# CompoundPeripheral.net
KiCad netlist of a schematic drawn in Altium Designer
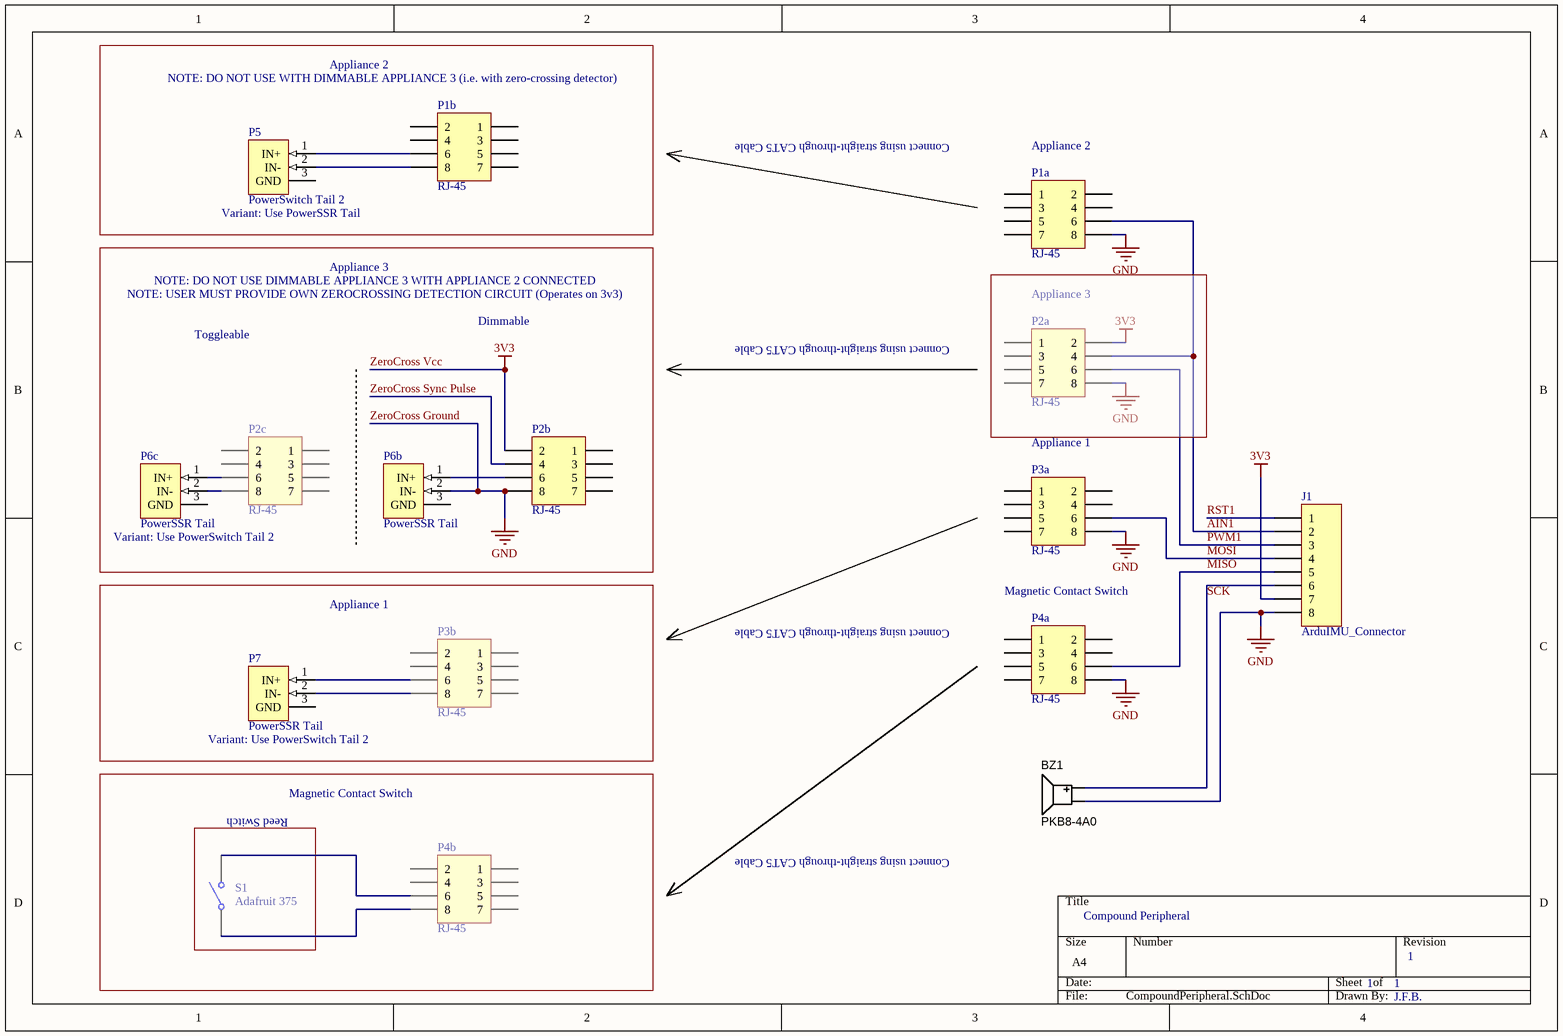
[diagram p0: CompoundPeripheral.SchDoc]

(export (version "E")
  (design (tool "Eeschema 10.0.6"))
  (components
    (comp (ref "BZ1")
      (value "PKB8-4A0")
      (footprint "BUZZER_12.0X8.5MM")
      (description "Speaker, Magnetic Transducer")
      (fields (field (name "MANUFACTURER PART NUMBER 1") "PKB8-4A0"))
      (libsource (lib "PBL - Electromechanical") (part "BZ_12x8.5x6.5_2kHz"))
    )
    (comp (ref "J1")
      (value "ArduIMU_Connector")
      (footprint "HDR1X8")
      (description "Header, 8-Pin")
      (fields (field (name "PUBLISHER") "Altium Limited"))
      (libsource (lib "Miscellaneous Connectors") (part "Header 8"))
    )
    (comp (ref "P1a")
      (value "RJ-45")
      (footprint "HDR2X4")
      (description "Header, 4-Pin, Dual row")
      (fields (field (name "PUBLISHER") "Altium Limited"))
      (libsource (lib "Miscellaneous Connectors") (part "Header 4X2"))
    )
    (comp (ref "P1b")
      (value "RJ-45")
      (footprint "HDR2X4")
      (description "Header, 4-Pin, Dual row")
      (fields (field (name "PUBLISHER") "Altium Limited"))
      (libsource (lib "") (part "Header 4X2_1"))
    )
    (comp (ref "P2a")
      (value "RJ-45")
      (footprint "HDR2X4")
      (description "Header, 4-Pin, Dual row")
      (fields (field (name "PUBLISHER") "Altium Limited"))
      (libsource (lib "Miscellaneous Connectors") (part "Header 4X2"))
    )
    (comp (ref "P2b")
      (value "RJ-45")
      (footprint "HDR2X4")
      (description "Header, 4-Pin, Dual row")
      (fields (field (name "PUBLISHER") "Altium Limited"))
      (libsource (lib "") (part "Header 4X2_1"))
    )
    (comp (ref "P2c")
      (value "RJ-45")
      (footprint "HDR2X4")
      (description "Header, 4-Pin, Dual row")
      (fields (field (name "PUBLISHER") "Altium Limited"))
      (libsource (lib "") (part "Header 4X2_1"))
    )
    (comp (ref "P3a")
      (value "RJ-45")
      (footprint "HDR2X4")
      (description "Header, 4-Pin, Dual row")
      (fields (field (name "PUBLISHER") "Altium Limited"))
      (libsource (lib "Miscellaneous Connectors") (part "Header 4X2"))
    )
    (comp (ref "P3b")
      (value "RJ-45")
      (footprint "HDR2X4")
      (description "Header, 4-Pin, Dual row")
      (fields (field (name "PUBLISHER") "Altium Limited"))
      (libsource (lib "") (part "Header 4X2_1"))
    )
    (comp (ref "P4a")
      (value "RJ-45")
      (footprint "HDR2X4")
      (description "Header, 4-Pin, Dual row")
      (fields (field (name "PUBLISHER") "Altium Limited"))
      (libsource (lib "Miscellaneous Connectors") (part "Header 4X2"))
    )
    (comp (ref "P4b")
      (value "RJ-45")
      (footprint "HDR2X4")
      (description "Header, 4-Pin, Dual row")
      (fields (field (name "PUBLISHER") "Altium Limited"))
      (libsource (lib "") (part "Header 4X2_1"))
    )
    (comp (ref "P5")
      (value "PowerSwitch Tail 2")
      (libsource (lib "CustomPeripherals") (part "PowerSwitch Tail 2"))
    )
    (comp (ref "P6b") (value "PowerSSR Tail") (libsource (lib "CustomPeripherals") (part "PowerSSR Tail")))
    (comp (ref "P6c") (value "PowerSSR Tail") (libsource (lib "CustomPeripherals") (part "PowerSSR Tail")))
    (comp (ref "P7") (value "PowerSSR Tail") (libsource (lib "CustomPeripherals") (part "PowerSSR Tail")))
    (comp (ref "S1")
      (value "Adafruit 375")
      (footprint "SPST-2")
      (description "Single-Pole, Single-Throw Switch")
      (fields (field (name "PUBLISHER") "Altium Limited"))
      (libsource (lib "Miscellaneous Devices") (part "SW-SPST"))
    )
  )
  (nets
    (net (code "1") (name "/AIN1") (class "Default")
      (node (ref "J1") (pin "2") (pinfunction "2_2") (pintype "passive"))
      (node (ref "P1a") (pin "6") (pinfunction "6_6") (pintype "passive"))
      (node (ref "P2a") (pin "4") (pinfunction "4_4") (pintype "passive"))
    )
    (net (code "2") (name "/MISO") (class "Default")
      (node (ref "J1") (pin "5") (pinfunction "5_5") (pintype "passive"))
      (node (ref "P4a") (pin "6") (pinfunction "6_6") (pintype "passive"))
    )
    (net (code "3") (name "/MOSI") (class "Default")
      (node (ref "J1") (pin "4") (pinfunction "4_4") (pintype "passive"))
      (node (ref "P3a") (pin "6") (pinfunction "6_6") (pintype "passive"))
    )
    (net (code "4") (name "/PWM1") (class "Default")
      (node (ref "J1") (pin "3") (pinfunction "3_3") (pintype "passive"))
      (node (ref "P2a") (pin "6") (pinfunction "6_6") (pintype "passive"))
    )
    (net (code "5") (name "/RST1") (class "Default")
      (node (ref "J1") (pin "1") (pinfunction "1_1") (pintype "passive"))
    )
    (net (code "6") (name "/SCK") (class "Default")
      (node (ref "BZ1") (pin "1") (pinfunction "Positive_1") (pintype "passive"))
      (node (ref "J1") (pin "6") (pinfunction "6_6") (pintype "passive"))
    )
    (net (code "7") (name "/ZeroCross Sync Pulse") (class "Default")
      (node (ref "P2b") (pin "4") (pinfunction "4_4") (pintype "passive"))
    )
    (net (code "8") (name "3V3") (class "Default")
      (node (ref "J1") (pin "7") (pinfunction "7_7") (pintype "passive"))
      (node (ref "P2a") (pin "2") (pinfunction "2_2") (pintype "passive"))
      (node (ref "P2b") (pin "2") (pinfunction "2_2") (pintype "passive"))
    )
    (net (code "9") (name "GND") (class "Default")
      (node (ref "BZ1") (pin "2") (pinfunction "Negative_2") (pintype "passive"))
      (node (ref "J1") (pin "8") (pinfunction "8_8") (pintype "passive"))
      (node (ref "P1a") (pin "8") (pinfunction "8_8") (pintype "passive"))
      (node (ref "P2a") (pin "8") (pinfunction "8_8") (pintype "passive"))
      (node (ref "P2b") (pin "8") (pinfunction "8_8") (pintype "passive"))
      (node (ref "P3a") (pin "8") (pinfunction "8_8") (pintype "passive"))
      (node (ref "P4a") (pin "8") (pinfunction "8_8") (pintype "passive"))
      (node (ref "P6b") (pin "2") (pinfunction "IN-_2") (pintype "input"))
    )
    (net (code "10") (name "Net-(P5-IN+)") (class "Default")
      (node (ref "P1b") (pin "6") (pinfunction "6_6") (pintype "passive"))
      (node (ref "P5") (pin "1") (pinfunction "IN+_1") (pintype "input"))
    )
    (net (code "11") (name "Net-(P5-IN-)") (class "Default")
      (node (ref "P1b") (pin "8") (pinfunction "8_8") (pintype "passive"))
      (node (ref "P5") (pin "2") (pinfunction "IN-_2") (pintype "input"))
    )
    (net (code "12") (name "Net-(P6b-IN+)") (class "Default")
      (node (ref "P2b") (pin "6") (pinfunction "6_6") (pintype "passive"))
      (node (ref "P6b") (pin "1") (pinfunction "IN+_1") (pintype "input"))
    )
    (net (code "13") (name "Net-(P6c-IN+)") (class "Default")
      (node (ref "P2c") (pin "6") (pinfunction "6_6") (pintype "passive"))
      (node (ref "P6c") (pin "1") (pinfunction "IN+_1") (pintype "input"))
    )
    (net (code "14") (name "Net-(P6c-IN-)") (class "Default")
      (node (ref "P2c") (pin "8") (pinfunction "8_8") (pintype "passive"))
      (node (ref "P6c") (pin "2") (pinfunction "IN-_2") (pintype "input"))
    )
    (net (code "15") (name "Net-(P7-IN+)") (class "Default")
      (node (ref "P3b") (pin "6") (pinfunction "6_6") (pintype "passive"))
      (node (ref "P7") (pin "1") (pinfunction "IN+_1") (pintype "input"))
    )
    (net (code "16") (name "Net-(P7-IN-)") (class "Default")
      (node (ref "P3b") (pin "8") (pinfunction "8_8") (pintype "passive"))
      (node (ref "P7") (pin "2") (pinfunction "IN-_2") (pintype "input"))
    )
    (net (code "17") (name "Net-(S1-COMMON)") (class "Default")
      (node (ref "P4b") (pin "8") (pinfunction "8_8") (pintype "passive"))
      (node (ref "S1") (pin "1") (pinfunction "COMMON_1") (pintype "passive"))
    )
    (net (code "18") (name "Net-(S1-NO)") (class "Default")
      (node (ref "P4b") (pin "6") (pinfunction "6_6") (pintype "passive"))
      (node (ref "S1") (pin "2") (pinfunction "NO_2") (pintype "passive"))
    )
    (net (code "19") (name "unconnected-(P1a-Pad1)") (class "Default")
      (node (ref "P1a") (pin "1") (pinfunction "1_1") (pintype "passive"))
    )
    (net (code "20") (name "unconnected-(P1a-Pad2)") (class "Default")
      (node (ref "P1a") (pin "2") (pinfunction "2_2") (pintype "passive"))
    )
    (net (code "21") (name "unconnected-(P1a-Pad3)") (class "Default")
      (node (ref "P1a") (pin "3") (pinfunction "3_3") (pintype "passive"))
    )
    (net (code "22") (name "unconnected-(P1a-Pad4)") (class "Default")
      (node (ref "P1a") (pin "4") (pinfunction "4_4") (pintype "passive"))
    )
    (net (code "23") (name "unconnected-(P1a-Pad5)") (class "Default")
      (node (ref "P1a") (pin "5") (pinfunction "5_5") (pintype "passive"))
    )
    (net (code "24") (name "unconnected-(P1a-Pad7)") (class "Default")
      (node (ref "P1a") (pin "7") (pinfunction "7_7") (pintype "passive"))
    )
    (net (code "25") (name "unconnected-(P1b-Pad1)") (class "Default")
      (node (ref "P1b") (pin "1") (pinfunction "1_1") (pintype "passive"))
    )
    (net (code "26") (name "unconnected-(P1b-Pad2)") (class "Default")
      (node (ref "P1b") (pin "2") (pinfunction "2_2") (pintype "passive"))
    )
    (net (code "27") (name "unconnected-(P1b-Pad3)") (class "Default")
      (node (ref "P1b") (pin "3") (pinfunction "3_3") (pintype "passive"))
    )
    (net (code "28") (name "unconnected-(P1b-Pad4)") (class "Default")
      (node (ref "P1b") (pin "4") (pinfunction "4_4") (pintype "passive"))
    )
    (net (code "29") (name "unconnected-(P1b-Pad5)") (class "Default")
      (node (ref "P1b") (pin "5") (pinfunction "5_5") (pintype "passive"))
    )
    (net (code "30") (name "unconnected-(P1b-Pad7)") (class "Default")
      (node (ref "P1b") (pin "7") (pinfunction "7_7") (pintype "passive"))
    )
    (net (code "31") (name "unconnected-(P2a-Pad1)") (class "Default")
      (node (ref "P2a") (pin "1") (pinfunction "1_1") (pintype "passive"))
    )
    (net (code "32") (name "unconnected-(P2a-Pad3)") (class "Default")
      (node (ref "P2a") (pin "3") (pinfunction "3_3") (pintype "passive"))
    )
    (net (code "33") (name "unconnected-(P2a-Pad5)") (class "Default")
      (node (ref "P2a") (pin "5") (pinfunction "5_5") (pintype "passive"))
    )
    (net (code "34") (name "unconnected-(P2a-Pad7)") (class "Default")
      (node (ref "P2a") (pin "7") (pinfunction "7_7") (pintype "passive"))
    )
    (net (code "35") (name "unconnected-(P2b-Pad1)") (class "Default")
      (node (ref "P2b") (pin "1") (pinfunction "1_1") (pintype "passive"))
    )
    (net (code "36") (name "unconnected-(P2b-Pad3)") (class "Default")
      (node (ref "P2b") (pin "3") (pinfunction "3_3") (pintype "passive"))
    )
    (net (code "37") (name "unconnected-(P2b-Pad5)") (class "Default")
      (node (ref "P2b") (pin "5") (pinfunction "5_5") (pintype "passive"))
    )
    (net (code "38") (name "unconnected-(P2b-Pad7)") (class "Default")
      (node (ref "P2b") (pin "7") (pinfunction "7_7") (pintype "passive"))
    )
    (net (code "39") (name "unconnected-(P2c-Pad1)") (class "Default")
      (node (ref "P2c") (pin "1") (pinfunction "1_1") (pintype "passive"))
    )
    (net (code "40") (name "unconnected-(P2c-Pad2)") (class "Default")
      (node (ref "P2c") (pin "2") (pinfunction "2_2") (pintype "passive"))
    )
    (net (code "41") (name "unconnected-(P2c-Pad3)") (class "Default")
      (node (ref "P2c") (pin "3") (pinfunction "3_3") (pintype "passive"))
    )
    (net (code "42") (name "unconnected-(P2c-Pad4)") (class "Default")
      (node (ref "P2c") (pin "4") (pinfunction "4_4") (pintype "passive"))
    )
    (net (code "43") (name "unconnected-(P2c-Pad5)") (class "Default")
      (node (ref "P2c") (pin "5") (pinfunction "5_5") (pintype "passive"))
    )
    (net (code "44") (name "unconnected-(P2c-Pad7)") (class "Default")
      (node (ref "P2c") (pin "7") (pinfunction "7_7") (pintype "passive"))
    )
    (net (code "45") (name "unconnected-(P3a-Pad1)") (class "Default")
      (node (ref "P3a") (pin "1") (pinfunction "1_1") (pintype "passive"))
    )
    (net (code "46") (name "unconnected-(P3a-Pad2)") (class "Default")
      (node (ref "P3a") (pin "2") (pinfunction "2_2") (pintype "passive"))
    )
    (net (code "47") (name "unconnected-(P3a-Pad3)") (class "Default")
      (node (ref "P3a") (pin "3") (pinfunction "3_3") (pintype "passive"))
    )
    (net (code "48") (name "unconnected-(P3a-Pad4)") (class "Default")
      (node (ref "P3a") (pin "4") (pinfunction "4_4") (pintype "passive"))
    )
    (net (code "49") (name "unconnected-(P3a-Pad5)") (class "Default")
      (node (ref "P3a") (pin "5") (pinfunction "5_5") (pintype "passive"))
    )
    (net (code "50") (name "unconnected-(P3a-Pad7)") (class "Default")
      (node (ref "P3a") (pin "7") (pinfunction "7_7") (pintype "passive"))
    )
    (net (code "51") (name "unconnected-(P3b-Pad1)") (class "Default")
      (node (ref "P3b") (pin "1") (pinfunction "1_1") (pintype "passive"))
    )
    (net (code "52") (name "unconnected-(P3b-Pad2)") (class "Default")
      (node (ref "P3b") (pin "2") (pinfunction "2_2") (pintype "passive"))
    )
    (net (code "53") (name "unconnected-(P3b-Pad3)") (class "Default")
      (node (ref "P3b") (pin "3") (pinfunction "3_3") (pintype "passive"))
    )
    (net (code "54") (name "unconnected-(P3b-Pad4)") (class "Default")
      (node (ref "P3b") (pin "4") (pinfunction "4_4") (pintype "passive"))
    )
    (net (code "55") (name "unconnected-(P3b-Pad5)") (class "Default")
      (node (ref "P3b") (pin "5") (pinfunction "5_5") (pintype "passive"))
    )
    (net (code "56") (name "unconnected-(P3b-Pad7)") (class "Default")
      (node (ref "P3b") (pin "7") (pinfunction "7_7") (pintype "passive"))
    )
    (net (code "57") (name "unconnected-(P4a-Pad1)") (class "Default")
      (node (ref "P4a") (pin "1") (pinfunction "1_1") (pintype "passive"))
    )
    (net (code "58") (name "unconnected-(P4a-Pad2)") (class "Default")
      (node (ref "P4a") (pin "2") (pinfunction "2_2") (pintype "passive"))
    )
    (net (code "59") (name "unconnected-(P4a-Pad3)") (class "Default")
      (node (ref "P4a") (pin "3") (pinfunction "3_3") (pintype "passive"))
    )
    (net (code "60") (name "unconnected-(P4a-Pad4)") (class "Default")
      (node (ref "P4a") (pin "4") (pinfunction "4_4") (pintype "passive"))
    )
    (net (code "61") (name "unconnected-(P4a-Pad5)") (class "Default")
      (node (ref "P4a") (pin "5") (pinfunction "5_5") (pintype "passive"))
    )
    (net (code "62") (name "unconnected-(P4a-Pad7)") (class "Default")
      (node (ref "P4a") (pin "7") (pinfunction "7_7") (pintype "passive"))
    )
    (net (code "63") (name "unconnected-(P4b-Pad1)") (class "Default")
      (node (ref "P4b") (pin "1") (pinfunction "1_1") (pintype "passive"))
    )
    (net (code "64") (name "unconnected-(P4b-Pad2)") (class "Default")
      (node (ref "P4b") (pin "2") (pinfunction "2_2") (pintype "passive"))
    )
    (net (code "65") (name "unconnected-(P4b-Pad3)") (class "Default")
      (node (ref "P4b") (pin "3") (pinfunction "3_3") (pintype "passive"))
    )
    (net (code "66") (name "unconnected-(P4b-Pad4)") (class "Default")
      (node (ref "P4b") (pin "4") (pinfunction "4_4") (pintype "passive"))
    )
    (net (code "67") (name "unconnected-(P4b-Pad5)") (class "Default")
      (node (ref "P4b") (pin "5") (pinfunction "5_5") (pintype "passive"))
    )
    (net (code "68") (name "unconnected-(P4b-Pad7)") (class "Default")
      (node (ref "P4b") (pin "7") (pinfunction "7_7") (pintype "passive"))
    )
    (net (code "69") (name "unconnected-(P5-GND-Pad3)") (class "Default")
      (node (ref "P5") (pin "3") (pinfunction "GND_3") (pintype "passive"))
    )
    (net (code "70") (name "unconnected-(P6b-GND-Pad3)") (class "Default")
      (node (ref "P6b") (pin "3") (pinfunction "GND_3") (pintype "passive"))
    )
    (net (code "71") (name "unconnected-(P6c-GND-Pad3)") (class "Default")
      (node (ref "P6c") (pin "3") (pinfunction "GND_3") (pintype "passive"))
    )
    (net (code "72") (name "unconnected-(P7-GND-Pad3)") (class "Default")
      (node (ref "P7") (pin "3") (pinfunction "GND_3") (pintype "passive"))
    )
  )
)
